# mains-protection-panel.net
KiCad netlist of a schematic drawn in EAGLE
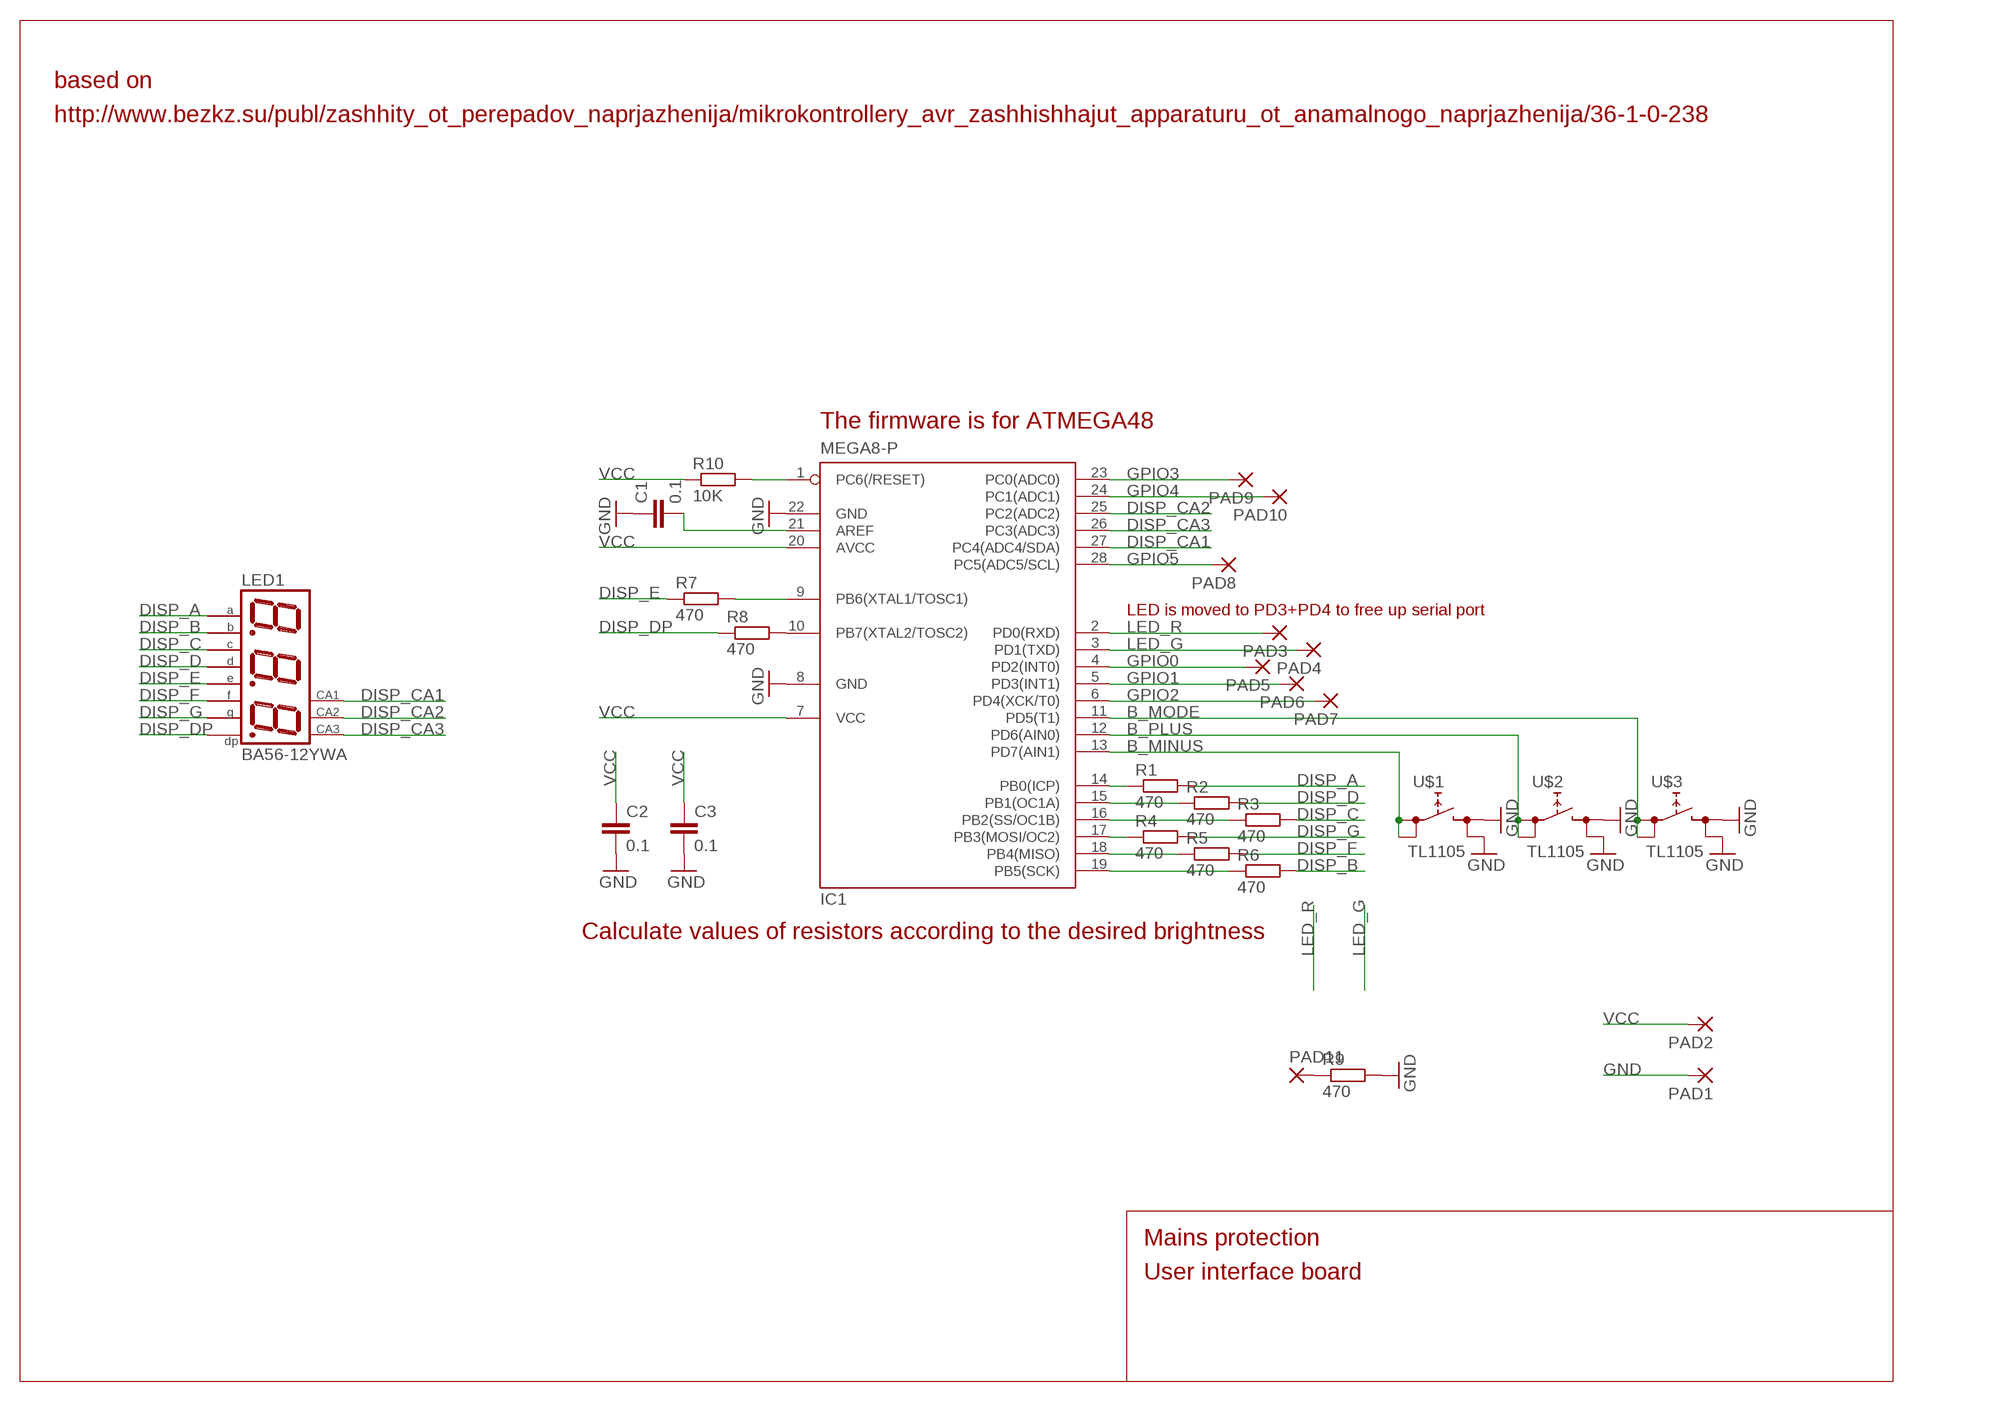
[diagram p0: schematic, sheet 1]

(export (version "E")
  (design (tool "Eeschema 10.0.6"))
  (components
    (comp (ref "C1")
      (value "0.1")
      (footprint "eagle-import:C1206")
      (libsource (lib "eagle-import") (part "C-EUC1206"))
    )
    (comp (ref "C2")
      (value "0.1")
      (footprint "eagle-import:C1206")
      (libsource (lib "eagle-import") (part "C-EUC1206"))
    )
    (comp (ref "C3")
      (value "0.1")
      (footprint "eagle-import:C1206")
      (libsource (lib "eagle-import") (part "C-EUC1206"))
    )
    (comp (ref "IC1")
      (value "MEGA8-P")
      (footprint "eagle-import:DIL28-3")
      (libsource (lib "eagle-import") (part "MEGA8-P"))
    )
    (comp (ref "LED1")
      (value "BA56-12YWA")
      (footprint "eagle-import:BX56-12")
      (libsource (lib "eagle-import") (part "B?56-12WAAY"))
    )
    (comp (ref "PAD1")
      (value "1,6/0,8")
      (footprint "eagle-import:1,6_0,8")
      (libsource (lib "eagle-import") (part "1,6/0,8"))
    )
    (comp (ref "PAD2")
      (value "1,6/0,8")
      (footprint "eagle-import:1,6_0,8")
      (libsource (lib "eagle-import") (part "1,6/0,8"))
    )
    (comp (ref "PAD3")
      (value "1,6/0,8")
      (footprint "eagle-import:1,6_0,8")
      (libsource (lib "eagle-import") (part "1,6/0,8"))
    )
    (comp (ref "PAD4")
      (value "1,6/0,8")
      (footprint "eagle-import:1,6_0,8")
      (libsource (lib "eagle-import") (part "1,6/0,8"))
    )
    (comp (ref "PAD5")
      (value "1,6/0,8")
      (footprint "eagle-import:1,6_0,8")
      (libsource (lib "eagle-import") (part "1,6/0,8"))
    )
    (comp (ref "PAD6")
      (value "1,6/0,8")
      (footprint "eagle-import:1,6_0,8")
      (libsource (lib "eagle-import") (part "1,6/0,8"))
    )
    (comp (ref "PAD7")
      (value "1,6/0,8")
      (footprint "eagle-import:1,6_0,8")
      (libsource (lib "eagle-import") (part "1,6/0,8"))
    )
    (comp (ref "PAD8")
      (value "1,6/0,8")
      (footprint "eagle-import:1,6_0,8")
      (libsource (lib "eagle-import") (part "1,6/0,8"))
    )
    (comp (ref "PAD9")
      (value "1,6/0,8")
      (footprint "eagle-import:1,6_0,8")
      (libsource (lib "eagle-import") (part "1,6/0,8"))
    )
    (comp (ref "PAD10")
      (value "1,6/0,8")
      (footprint "eagle-import:1,6_0,8")
      (libsource (lib "eagle-import") (part "1,6/0,8"))
    )
    (comp (ref "PAD11")
      (value "1,6/0,8")
      (footprint "eagle-import:1,6_0,8")
      (libsource (lib "eagle-import") (part "1,6/0,8"))
    )
    (comp (ref "R1")
      (value "470")
      (footprint "eagle-import:R0805")
      (libsource (lib "eagle-import") (part "R-EU_R0805"))
    )
    (comp (ref "R2")
      (value "470")
      (footprint "eagle-import:R0805")
      (libsource (lib "eagle-import") (part "R-EU_R0805"))
    )
    (comp (ref "R3")
      (value "470")
      (footprint "eagle-import:R0805")
      (libsource (lib "eagle-import") (part "R-EU_R0805"))
    )
    (comp (ref "R4")
      (value "470")
      (footprint "eagle-import:R0805")
      (libsource (lib "eagle-import") (part "R-EU_R0805"))
    )
    (comp (ref "R5")
      (value "470")
      (footprint "eagle-import:R0805")
      (libsource (lib "eagle-import") (part "R-EU_R0805"))
    )
    (comp (ref "R6")
      (value "470")
      (footprint "eagle-import:R0805")
      (libsource (lib "eagle-import") (part "R-EU_R0805"))
    )
    (comp (ref "R7")
      (value "470")
      (footprint "eagle-import:R0805")
      (libsource (lib "eagle-import") (part "R-EU_R0805"))
    )
    (comp (ref "R8")
      (value "470")
      (footprint "eagle-import:R0805")
      (libsource (lib "eagle-import") (part "R-EU_R0805"))
    )
    (comp (ref "R9")
      (value "470")
      (footprint "eagle-import:R0805")
      (libsource (lib "eagle-import") (part "R-EU_R0805"))
    )
    (comp (ref "R10")
      (value "10K")
      (footprint "eagle-import:R0805")
      (libsource (lib "eagle-import") (part "R-EU_R0805"))
    )
    (comp (ref "U$1")
      (value "TL1105")
      (footprint "eagle-import:LARGE")
      (libsource (lib "eagle-import") (part "TL1105"))
    )
    (comp (ref "U$2")
      (value "TL1105")
      (footprint "eagle-import:LARGE")
      (libsource (lib "eagle-import") (part "TL1105"))
    )
    (comp (ref "U$3")
      (value "TL1105")
      (footprint "eagle-import:LARGE")
      (libsource (lib "eagle-import") (part "TL1105"))
    )
  )
  (nets
    (net (code "1") (name "/B_MINUS") (class "Default")
      (node (ref "IC1") (pin "13") (pinfunction "PD7(AIN1)_13") (pintype "bidirectional"))
      (node (ref "U$1") (pin "P$1") (pinfunction "0_P$1") (pintype "passive"))
      (node (ref "U$1") (pin "P$2") (pinfunction "0_P$2") (pintype "passive"))
    )
    (net (code "2") (name "/B_MODE") (class "Default")
      (node (ref "IC1") (pin "11") (pinfunction "PD5(T1)_11") (pintype "bidirectional"))
      (node (ref "U$3") (pin "P$1") (pinfunction "0_P$1") (pintype "passive"))
      (node (ref "U$3") (pin "P$2") (pinfunction "0_P$2") (pintype "passive"))
    )
    (net (code "3") (name "/B_PLUS") (class "Default")
      (node (ref "IC1") (pin "12") (pinfunction "PD6(AIN0)_12") (pintype "bidirectional"))
      (node (ref "U$2") (pin "P$1") (pinfunction "0_P$1") (pintype "passive"))
      (node (ref "U$2") (pin "P$2") (pinfunction "0_P$2") (pintype "passive"))
    )
    (net (code "4") (name "/DISP_A") (class "Default")
      (node (ref "LED1") (pin "11") (pinfunction "A_11") (pintype "passive"))
      (node (ref "R1") (pin "2") (pinfunction "2_2") (pintype "passive"))
    )
    (net (code "5") (name "/DISP_B") (class "Default")
      (node (ref "LED1") (pin "7") (pinfunction "B_7") (pintype "passive"))
      (node (ref "R6") (pin "2") (pinfunction "2_2") (pintype "passive"))
    )
    (net (code "6") (name "/DISP_C") (class "Default")
      (node (ref "LED1") (pin "4") (pinfunction "C_4") (pintype "passive"))
      (node (ref "R3") (pin "2") (pinfunction "2_2") (pintype "passive"))
    )
    (net (code "7") (name "/DISP_CA1") (class "Default")
      (node (ref "IC1") (pin "27") (pinfunction "PC4(ADC4/SDA)_27") (pintype "bidirectional"))
      (node (ref "LED1") (pin "12") (pinfunction "CA_12") (pintype "passive"))
    )
    (net (code "8") (name "/DISP_CA2") (class "Default")
      (node (ref "IC1") (pin "25") (pinfunction "PC2(ADC2)_25") (pintype "bidirectional"))
      (node (ref "LED1") (pin "9") (pinfunction "CA_9") (pintype "passive"))
    )
    (net (code "9") (name "/DISP_CA3") (class "Default")
      (node (ref "IC1") (pin "26") (pinfunction "PC3(ADC3)_26") (pintype "bidirectional"))
      (node (ref "LED1") (pin "8") (pinfunction "CA_8") (pintype "passive"))
    )
    (net (code "10") (name "/DISP_D") (class "Default")
      (node (ref "LED1") (pin "2") (pinfunction "D_2") (pintype "passive"))
      (node (ref "R2") (pin "2") (pinfunction "2_2") (pintype "passive"))
    )
    (net (code "11") (name "/DISP_DP") (class "Default")
      (node (ref "LED1") (pin "3") (pinfunction "DP_3") (pintype "passive"))
      (node (ref "R8") (pin "1") (pinfunction "1_1") (pintype "passive"))
    )
    (net (code "12") (name "/DISP_E") (class "Default")
      (node (ref "LED1") (pin "1") (pinfunction "E_1") (pintype "passive"))
      (node (ref "R7") (pin "1") (pinfunction "1_1") (pintype "passive"))
    )
    (net (code "13") (name "/DISP_F") (class "Default")
      (node (ref "LED1") (pin "10") (pinfunction "F_10") (pintype "passive"))
      (node (ref "R5") (pin "2") (pinfunction "2_2") (pintype "passive"))
    )
    (net (code "14") (name "/DISP_G") (class "Default")
      (node (ref "LED1") (pin "5") (pinfunction "G_5") (pintype "passive"))
      (node (ref "R4") (pin "2") (pinfunction "2_2") (pintype "passive"))
    )
    (net (code "15") (name "/GPIO0") (class "Default")
      (node (ref "IC1") (pin "4") (pinfunction "PD2(INT0)_4") (pintype "bidirectional"))
      (node (ref "PAD5") (pin "1") (pinfunction "P_1") (pintype "passive"))
    )
    (net (code "16") (name "/GPIO1") (class "Default")
      (node (ref "IC1") (pin "5") (pinfunction "PD3(INT1)_5") (pintype "bidirectional"))
      (node (ref "PAD6") (pin "1") (pinfunction "P_1") (pintype "passive"))
    )
    (net (code "17") (name "/GPIO2") (class "Default")
      (node (ref "IC1") (pin "6") (pinfunction "PD4(XCK/T0)_6") (pintype "bidirectional"))
      (node (ref "PAD7") (pin "1") (pinfunction "P_1") (pintype "passive"))
    )
    (net (code "18") (name "/GPIO3") (class "Default")
      (node (ref "IC1") (pin "23") (pinfunction "PC0(ADC0)_23") (pintype "bidirectional"))
      (node (ref "PAD9") (pin "1") (pinfunction "P_1") (pintype "passive"))
    )
    (net (code "19") (name "/GPIO4") (class "Default")
      (node (ref "IC1") (pin "24") (pinfunction "PC1(ADC1)_24") (pintype "bidirectional"))
      (node (ref "PAD10") (pin "1") (pinfunction "P_1") (pintype "passive"))
    )
    (net (code "20") (name "/GPIO5") (class "Default")
      (node (ref "IC1") (pin "28") (pinfunction "PC5(ADC5/SCL)_28") (pintype "bidirectional"))
      (node (ref "PAD8") (pin "1") (pinfunction "P_1") (pintype "passive"))
    )
    (net (code "21") (name "/LED_G") (class "Default")
      (node (ref "IC1") (pin "3") (pinfunction "PD1(TXD)_3") (pintype "bidirectional"))
      (node (ref "PAD4") (pin "1") (pinfunction "P_1") (pintype "passive"))
    )
    (net (code "22") (name "/LED_R") (class "Default")
      (node (ref "IC1") (pin "2") (pinfunction "PD0(RXD)_2") (pintype "bidirectional"))
      (node (ref "PAD3") (pin "1") (pinfunction "P_1") (pintype "passive"))
    )
    (net (code "23") (name "/VCC") (class "Default")
      (node (ref "C2") (pin "1") (pinfunction "1_1") (pintype "passive"))
      (node (ref "C3") (pin "1") (pinfunction "1_1") (pintype "passive"))
      (node (ref "IC1") (pin "20") (pinfunction "AVCC_20") (pintype "power_in"))
      (node (ref "IC1") (pin "7") (pinfunction "VCC_7") (pintype "power_in"))
      (node (ref "PAD2") (pin "1") (pinfunction "P_1") (pintype "passive"))
      (node (ref "R10") (pin "1") (pinfunction "1_1") (pintype "passive"))
    )
    (net (code "24") (name "GND") (class "Default")
      (node (ref "C1") (pin "1") (pinfunction "1_1") (pintype "passive"))
      (node (ref "C2") (pin "2") (pinfunction "2_2") (pintype "passive"))
      (node (ref "C3") (pin "2") (pinfunction "2_2") (pintype "passive"))
      (node (ref "IC1") (pin "22") (pinfunction "GND_22") (pintype "power_in"))
      (node (ref "IC1") (pin "8") (pinfunction "GND_8") (pintype "power_in"))
      (node (ref "PAD1") (pin "1") (pinfunction "P_1") (pintype "passive"))
      (node (ref "R9") (pin "2") (pinfunction "2_2") (pintype "passive"))
      (node (ref "U$1") (pin "P$3") (pinfunction "1_P$3") (pintype "passive"))
      (node (ref "U$1") (pin "P$4") (pinfunction "1_P$4") (pintype "passive"))
      (node (ref "U$2") (pin "P$3") (pinfunction "1_P$3") (pintype "passive"))
      (node (ref "U$2") (pin "P$4") (pinfunction "1_P$4") (pintype "passive"))
      (node (ref "U$3") (pin "P$3") (pinfunction "1_P$3") (pintype "passive"))
      (node (ref "U$3") (pin "P$4") (pinfunction "1_P$4") (pintype "passive"))
    )
    (net (code "25") (name "Net-(IC1-AREF)") (class "Default")
      (node (ref "C1") (pin "2") (pinfunction "2_2") (pintype "passive"))
      (node (ref "IC1") (pin "21") (pinfunction "AREF_21") (pintype "passive"))
    )
    (net (code "26") (name "Net-(IC1-PB0(ICP))") (class "Default")
      (node (ref "IC1") (pin "14") (pinfunction "PB0(ICP)_14") (pintype "bidirectional"))
      (node (ref "R1") (pin "1") (pinfunction "1_1") (pintype "passive"))
    )
    (net (code "27") (name "Net-(IC1-PB1(OC1A))") (class "Default")
      (node (ref "IC1") (pin "15") (pinfunction "PB1(OC1A)_15") (pintype "bidirectional"))
      (node (ref "R2") (pin "1") (pinfunction "1_1") (pintype "passive"))
    )
    (net (code "28") (name "Net-(IC1-PB2(SS{slash}OC1B))") (class "Default")
      (node (ref "IC1") (pin "16") (pinfunction "PB2(SS/OC1B)_16") (pintype "bidirectional"))
      (node (ref "R3") (pin "1") (pinfunction "1_1") (pintype "passive"))
    )
    (net (code "29") (name "Net-(IC1-PB3(MOSI{slash}OC2))") (class "Default")
      (node (ref "IC1") (pin "17") (pinfunction "PB3(MOSI/OC2)_17") (pintype "bidirectional"))
      (node (ref "R4") (pin "1") (pinfunction "1_1") (pintype "passive"))
    )
    (net (code "30") (name "Net-(IC1-PB4(MISO))") (class "Default")
      (node (ref "IC1") (pin "18") (pinfunction "PB4(MISO)_18") (pintype "bidirectional"))
      (node (ref "R5") (pin "1") (pinfunction "1_1") (pintype "passive"))
    )
    (net (code "31") (name "Net-(IC1-PB5(SCK))") (class "Default")
      (node (ref "IC1") (pin "19") (pinfunction "PB5(SCK)_19") (pintype "bidirectional"))
      (node (ref "R6") (pin "1") (pinfunction "1_1") (pintype "passive"))
    )
    (net (code "32") (name "Net-(IC1-PB6(XTAL1{slash}TOSC1))") (class "Default")
      (node (ref "IC1") (pin "9") (pinfunction "PB6(XTAL1/TOSC1)_9") (pintype "bidirectional"))
      (node (ref "R7") (pin "2") (pinfunction "2_2") (pintype "passive"))
    )
    (net (code "33") (name "Net-(IC1-PB7(XTAL2{slash}TOSC2))") (class "Default")
      (node (ref "IC1") (pin "10") (pinfunction "PB7(XTAL2/TOSC2)_10") (pintype "bidirectional"))
      (node (ref "R8") (pin "2") (pinfunction "2_2") (pintype "passive"))
    )
    (net (code "34") (name "Net-(IC1-PC6({slash}RESET))") (class "Default")
      (node (ref "IC1") (pin "1") (pinfunction "PC6(/RESET)_1") (pintype "bidirectional"))
      (node (ref "R10") (pin "2") (pinfunction "2_2") (pintype "passive"))
    )
    (net (code "35") (name "Net-(PAD11-P)") (class "Default")
      (node (ref "PAD11") (pin "1") (pinfunction "P_1") (pintype "passive"))
      (node (ref "R9") (pin "1") (pinfunction "1_1") (pintype "passive"))
    )
  )
)
